# inverter.net
KiCad netlist of a schematic drawn in EAGLE
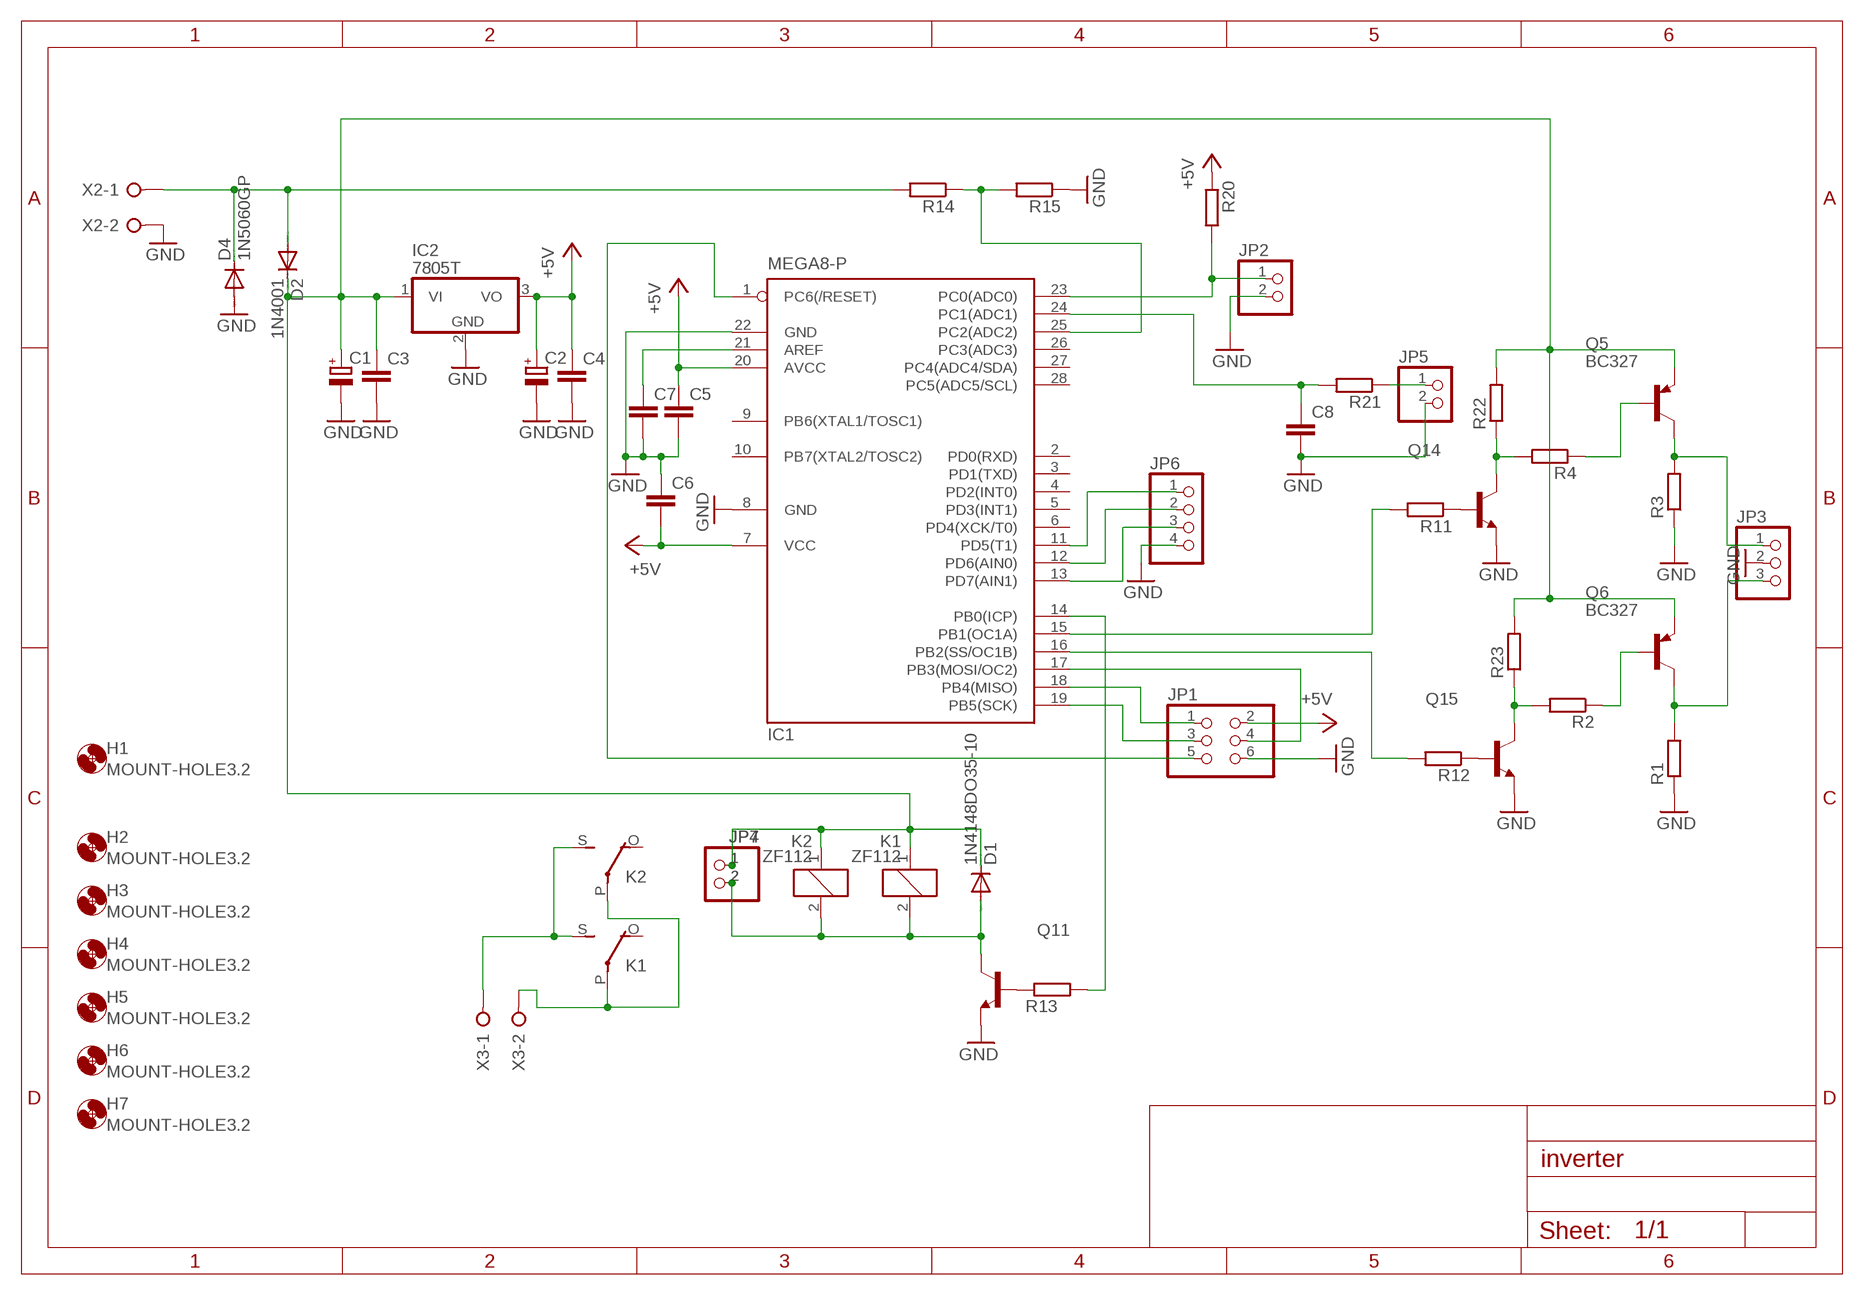
[diagram p0: schematic, sheet 1]

(export (version "E")
  (design (tool "Eeschema 10.0.6"))
  (components
    (comp (ref "C1")
      (value "CPOL-EUE7.5-16")
      (footprint "eagle-import:E7,5-16")
      (libsource (lib "eagle-import") (part "CPOL-EUE7.5-16"))
    )
    (comp (ref "C2")
      (value "CPOL-EUE2.5-6")
      (footprint "eagle-import:E2,5-6")
      (libsource (lib "eagle-import") (part "CPOL-EUE2.5-6"))
    )
    (comp (ref "C3")
      (value "C-EU050-025X075")
      (footprint "eagle-import:C050-025X075")
      (libsource (lib "eagle-import") (part "C-EU050-025X075"))
    )
    (comp (ref "C4")
      (value "C-EU050-025X075")
      (footprint "eagle-import:C050-025X075")
      (libsource (lib "eagle-import") (part "C-EU050-025X075"))
    )
    (comp (ref "C5")
      (value "C-EU050-025X075")
      (footprint "eagle-import:C050-025X075")
      (libsource (lib "eagle-import") (part "C-EU050-025X075"))
    )
    (comp (ref "C6")
      (value "C-EU050-025X075")
      (footprint "eagle-import:C050-025X075")
      (libsource (lib "eagle-import") (part "C-EU050-025X075"))
    )
    (comp (ref "C7")
      (value "C-EU050-025X075")
      (footprint "eagle-import:C050-025X075")
      (libsource (lib "eagle-import") (part "C-EU050-025X075"))
    )
    (comp (ref "C8")
      (value "C-EU050-025X075")
      (footprint "eagle-import:C050-025X075")
      (libsource (lib "eagle-import") (part "C-EU050-025X075"))
    )
    (comp (ref "D1")
      (value "1N4148DO35-10")
      (footprint "eagle-import:DO35-10")
      (libsource (lib "eagle-import") (part "1N4148DO35-10"))
    )
    (comp (ref "D2")
      (value "1N4001")
      (footprint "eagle-import:DO35-10")
      (libsource (lib "eagle-import") (part "1N4148DO35-10"))
    )
    (comp (ref "D4")
      (value "1N5060GP")
      (footprint "eagle-import:DO15-12")
      (libsource (lib "eagle-import") (part "1N5060GP"))
    )
    (comp (ref "H1")
      (value "MOUNT-HOLE3.2")
      (footprint "eagle-import:3,2")
      (libsource (lib "eagle-import") (part "MOUNT-HOLE3.2"))
    )
    (comp (ref "H2")
      (value "MOUNT-HOLE3.2")
      (footprint "eagle-import:3,2")
      (libsource (lib "eagle-import") (part "MOUNT-HOLE3.2"))
    )
    (comp (ref "H3")
      (value "MOUNT-HOLE3.2")
      (footprint "eagle-import:3,2")
      (libsource (lib "eagle-import") (part "MOUNT-HOLE3.2"))
    )
    (comp (ref "H4")
      (value "MOUNT-HOLE3.2")
      (footprint "eagle-import:3,2")
      (libsource (lib "eagle-import") (part "MOUNT-HOLE3.2"))
    )
    (comp (ref "H5")
      (value "MOUNT-HOLE3.2")
      (footprint "eagle-import:3,2")
      (libsource (lib "eagle-import") (part "MOUNT-HOLE3.2"))
    )
    (comp (ref "H6")
      (value "MOUNT-HOLE3.2")
      (footprint "eagle-import:3,2")
      (libsource (lib "eagle-import") (part "MOUNT-HOLE3.2"))
    )
    (comp (ref "H7")
      (value "MOUNT-HOLE3.2")
      (footprint "eagle-import:3,2")
      (libsource (lib "eagle-import") (part "MOUNT-HOLE3.2"))
    )
    (comp (ref "IC1")
      (value "MEGA8-P")
      (footprint "eagle-import:DIL28-3")
      (libsource (lib "eagle-import") (part "MEGA8-P"))
    )
    (comp (ref "IC2")
      (value "7805T")
      (footprint "eagle-import:TO220H")
      (libsource (lib "eagle-import") (part "78T05"))
    )
    (comp (ref "JP1")
      (value "PINHD-2X3")
      (footprint "eagle-import:2X03")
      (libsource (lib "eagle-import") (part "PINHD-2X3"))
    )
    (comp (ref "JP2")
      (value "PINHD-1X2")
      (footprint "eagle-import:1X02")
      (libsource (lib "eagle-import") (part "PINHD-1X2"))
    )
    (comp (ref "JP3")
      (value "PINHD-1X3")
      (footprint "eagle-import:1X03")
      (libsource (lib "eagle-import") (part "PINHD-1X3"))
    )
    (comp (ref "JP4")
      (value "PINHD-1X2")
      (footprint "eagle-import:1X02")
      (libsource (lib "eagle-import") (part "PINHD-1X2"))
    )
    (comp (ref "JP5")
      (value "PINHD-1X2")
      (footprint "eagle-import:1X02")
      (libsource (lib "eagle-import") (part "PINHD-1X2"))
    )
    (comp (ref "JP6")
      (value "PINHD-1X4")
      (footprint "eagle-import:1X04")
      (libsource (lib "eagle-import") (part "PINHD-1X4"))
    )
    (comp (ref "JP7")
      (value "PINHD-1X2")
      (footprint "eagle-import:1X02")
      (libsource (lib "eagle-import") (part "PINHD-1X2"))
    )
    (comp (ref "K1")
      (value "ZF112")
      (footprint "eagle-import:ZF112")
      (libsource (lib "eagle-import") (part "ZF112"))
    )
    (comp (ref "K2")
      (value "ZF112")
      (footprint "eagle-import:ZF112")
      (libsource (lib "eagle-import") (part "ZF112"))
    )
    (comp (ref "Q5")
      (value "BC327")
      (footprint "eagle-import:TO92-EBC")
      (libsource (lib "eagle-import") (part "BC327"))
    )
    (comp (ref "Q6")
      (value "BC327")
      (footprint "eagle-import:TO92-EBC")
      (libsource (lib "eagle-import") (part "BC327"))
    )
    (comp (ref "Q11")
      (value "BC547-NPN-TO92-CBE")
      (footprint "eagle-import:TO92-CBE")
      (libsource (lib "eagle-import") (part "-NPN-TO92-CBEBC547"))
    )
    (comp (ref "Q14")
      (value "BC547-NPN-TO92-CBE")
      (footprint "eagle-import:TO92-CBE")
      (libsource (lib "eagle-import") (part "-NPN-TO92-CBEBC547"))
    )
    (comp (ref "Q15")
      (value "BC547-NPN-TO92-CBE")
      (footprint "eagle-import:TO92-CBE")
      (libsource (lib "eagle-import") (part "-NPN-TO92-CBEBC547"))
    )
    (comp (ref "R1")
      (value "R-EU_0207/5V")
      (footprint "eagle-import:0207_5V")
      (libsource (lib "eagle-import") (part "R-EU_0207/5V"))
    )
    (comp (ref "R2")
      (value "R-EU_0207/2V")
      (footprint "eagle-import:0207_2V")
      (libsource (lib "eagle-import") (part "R-EU_0207/2V"))
    )
    (comp (ref "R3")
      (value "R-EU_0207/5V")
      (footprint "eagle-import:0207_5V")
      (libsource (lib "eagle-import") (part "R-EU_0207/5V"))
    )
    (comp (ref "R4")
      (value "R-EU_0207/2V")
      (footprint "eagle-import:0207_2V")
      (libsource (lib "eagle-import") (part "R-EU_0207/2V"))
    )
    (comp (ref "R11")
      (value "R-EU_0207/5V")
      (footprint "eagle-import:0207_5V")
      (libsource (lib "eagle-import") (part "R-EU_0207/5V"))
    )
    (comp (ref "R12")
      (value "R-EU_0207/5V")
      (footprint "eagle-import:0207_5V")
      (libsource (lib "eagle-import") (part "R-EU_0207/5V"))
    )
    (comp (ref "R13")
      (value "R-EU_0207/2V")
      (footprint "eagle-import:0207_2V")
      (libsource (lib "eagle-import") (part "R-EU_0207/2V"))
    )
    (comp (ref "R14")
      (value "R-EU_0207/10")
      (footprint "eagle-import:0207_10")
      (libsource (lib "eagle-import") (part "R-EU_0207/10"))
    )
    (comp (ref "R15")
      (value "R-EU_0207/10")
      (footprint "eagle-import:0207_10")
      (libsource (lib "eagle-import") (part "R-EU_0207/10"))
    )
    (comp (ref "R20")
      (value "R-EU_0207/10")
      (footprint "eagle-import:0207_10")
      (libsource (lib "eagle-import") (part "R-EU_0207/10"))
    )
    (comp (ref "R21")
      (value "R-EU_0207/2V")
      (footprint "eagle-import:0207_2V")
      (libsource (lib "eagle-import") (part "R-EU_0207/2V"))
    )
    (comp (ref "R22")
      (value "R-EU_0207/10")
      (footprint "eagle-import:0207_10")
      (libsource (lib "eagle-import") (part "R-EU_0207/10"))
    )
    (comp (ref "R23")
      (value "R-EU_0207/10")
      (footprint "eagle-import:0207_10")
      (libsource (lib "eagle-import") (part "R-EU_0207/10"))
    )
    (comp (ref "X2")
      (value "W237-02P")
      (footprint "eagle-import:W237-132")
      (libsource (lib "eagle-import") (part "W237-02P"))
    )
    (comp (ref "X3")
      (value "W237-02P")
      (footprint "eagle-import:W237-132")
      (libsource (lib "eagle-import") (part "W237-02P"))
    )
  )
  (nets
    (net (code "1") (name "+5V") (class "Default")
      (node (ref "C2") (pin "+") (pinfunction "+_+") (pintype "passive"))
      (node (ref "C4") (pin "1") (pinfunction "1_1") (pintype "passive"))
      (node (ref "C5") (pin "1") (pinfunction "1_1") (pintype "passive"))
      (node (ref "C6") (pin "2") (pinfunction "2_2") (pintype "passive"))
      (node (ref "IC1") (pin "20") (pinfunction "AVCC_20") (pintype "power_in"))
      (node (ref "IC1") (pin "7") (pinfunction "VCC_7") (pintype "power_in"))
      (node (ref "IC2") (pin "3") (pinfunction "VO_3") (pintype "passive"))
      (node (ref "JP1") (pin "2") (pinfunction "2_2") (pintype "passive"))
      (node (ref "R20") (pin "1") (pinfunction "1_1") (pintype "passive"))
    )
    (net (code "2") (name "GND") (class "Default")
      (node (ref "C1") (pin "-") (pinfunction "-_-") (pintype "passive"))
      (node (ref "C2") (pin "-") (pinfunction "-_-") (pintype "passive"))
      (node (ref "C3") (pin "2") (pinfunction "2_2") (pintype "passive"))
      (node (ref "C4") (pin "2") (pinfunction "2_2") (pintype "passive"))
      (node (ref "C5") (pin "2") (pinfunction "2_2") (pintype "passive"))
      (node (ref "C6") (pin "1") (pinfunction "1_1") (pintype "passive"))
      (node (ref "C7") (pin "2") (pinfunction "2_2") (pintype "passive"))
      (node (ref "C8") (pin "2") (pinfunction "2_2") (pintype "passive"))
      (node (ref "D4") (pin "A") (pinfunction "A_A") (pintype "passive"))
      (node (ref "IC1") (pin "22") (pinfunction "GND_22") (pintype "power_in"))
      (node (ref "IC1") (pin "8") (pinfunction "GND_8") (pintype "power_in"))
      (node (ref "IC2") (pin "2") (pinfunction "GND_2") (pintype "passive"))
      (node (ref "JP1") (pin "6") (pinfunction "6_6") (pintype "passive"))
      (node (ref "JP2") (pin "2") (pinfunction "2_2") (pintype "passive"))
      (node (ref "JP3") (pin "2") (pinfunction "2_2") (pintype "passive"))
      (node (ref "JP5") (pin "2") (pinfunction "2_2") (pintype "passive"))
      (node (ref "JP6") (pin "4") (pinfunction "4_4") (pintype "passive"))
      (node (ref "Q11") (pin "E") (pinfunction "E_E") (pintype "passive"))
      (node (ref "Q14") (pin "E") (pinfunction "E_E") (pintype "passive"))
      (node (ref "Q15") (pin "E") (pinfunction "E_E") (pintype "passive"))
      (node (ref "R1") (pin "1") (pinfunction "1_1") (pintype "passive"))
      (node (ref "R15") (pin "1") (pinfunction "1_1") (pintype "passive"))
      (node (ref "R3") (pin "1") (pinfunction "1_1") (pintype "passive"))
      (node (ref "X2") (pin "2") (pinfunction "KL_2") (pintype "passive"))
    )
    (net (code "3") (name "Net-(D1-PadA)") (class "Default")
      (node (ref "D1") (pin "A") (pinfunction "A_A") (pintype "passive"))
      (node (ref "JP4") (pin "2") (pinfunction "2_2") (pintype "passive"))
      (node (ref "JP7") (pin "2") (pinfunction "2_2") (pintype "passive"))
      (node (ref "K1") (pin "2") (pinfunction "2_2") (pintype "passive"))
      (node (ref "K2") (pin "2") (pinfunction "2_2") (pintype "passive"))
      (node (ref "Q11") (pin "C") (pinfunction "C_C") (pintype "passive"))
    )
    (net (code "4") (name "Net-(IC1-AREF)") (class "Default")
      (node (ref "C7") (pin "1") (pinfunction "1_1") (pintype "passive"))
      (node (ref "IC1") (pin "21") (pinfunction "AREF_21") (pintype "passive"))
    )
    (net (code "5") (name "Net-(IC1-PB0(ICP))") (class "Default")
      (node (ref "IC1") (pin "14") (pinfunction "PB0(ICP)_14") (pintype "bidirectional"))
      (node (ref "R13") (pin "2") (pinfunction "2_2") (pintype "passive"))
    )
    (net (code "6") (name "Net-(IC1-PB1(OC1A))") (class "Default")
      (node (ref "IC1") (pin "15") (pinfunction "PB1(OC1A)_15") (pintype "bidirectional"))
      (node (ref "R11") (pin "2") (pinfunction "2_2") (pintype "passive"))
    )
    (net (code "7") (name "Net-(IC1-PB2(SS{slash}OC1B))") (class "Default")
      (node (ref "IC1") (pin "16") (pinfunction "PB2(SS/OC1B)_16") (pintype "bidirectional"))
      (node (ref "R12") (pin "2") (pinfunction "2_2") (pintype "passive"))
    )
    (net (code "8") (name "Net-(IC1-PB3(MOSI{slash}OC2))") (class "Default")
      (node (ref "IC1") (pin "17") (pinfunction "PB3(MOSI/OC2)_17") (pintype "bidirectional"))
      (node (ref "JP1") (pin "4") (pinfunction "4_4") (pintype "passive"))
    )
    (net (code "9") (name "Net-(IC1-PB4(MISO))") (class "Default")
      (node (ref "IC1") (pin "18") (pinfunction "PB4(MISO)_18") (pintype "bidirectional"))
      (node (ref "JP1") (pin "1") (pinfunction "1_1") (pintype "passive"))
    )
    (net (code "10") (name "Net-(IC1-PB5(SCK))") (class "Default")
      (node (ref "IC1") (pin "19") (pinfunction "PB5(SCK)_19") (pintype "bidirectional"))
      (node (ref "JP1") (pin "3") (pinfunction "3_3") (pintype "passive"))
    )
    (net (code "11") (name "Net-(IC1-PC0(ADC0))") (class "Default")
      (node (ref "IC1") (pin "23") (pinfunction "PC0(ADC0)_23") (pintype "bidirectional"))
      (node (ref "JP2") (pin "1") (pinfunction "1_1") (pintype "passive"))
      (node (ref "R20") (pin "2") (pinfunction "2_2") (pintype "passive"))
    )
    (net (code "12") (name "Net-(IC1-PC1(ADC1))") (class "Default")
      (node (ref "C8") (pin "1") (pinfunction "1_1") (pintype "passive"))
      (node (ref "IC1") (pin "24") (pinfunction "PC1(ADC1)_24") (pintype "bidirectional"))
      (node (ref "R21") (pin "2") (pinfunction "2_2") (pintype "passive"))
    )
    (net (code "13") (name "Net-(IC1-PC2(ADC2))") (class "Default")
      (node (ref "IC1") (pin "25") (pinfunction "PC2(ADC2)_25") (pintype "bidirectional"))
      (node (ref "R14") (pin "1") (pinfunction "1_1") (pintype "passive"))
      (node (ref "R15") (pin "2") (pinfunction "2_2") (pintype "passive"))
    )
    (net (code "14") (name "Net-(IC1-PC6({slash}RESET))") (class "Default")
      (node (ref "IC1") (pin "1") (pinfunction "PC6(/RESET)_1") (pintype "bidirectional"))
      (node (ref "JP1") (pin "5") (pinfunction "5_5") (pintype "passive"))
    )
    (net (code "15") (name "Net-(IC1-PD5(T1))") (class "Default")
      (node (ref "IC1") (pin "11") (pinfunction "PD5(T1)_11") (pintype "bidirectional"))
      (node (ref "JP6") (pin "1") (pinfunction "1_1") (pintype "passive"))
    )
    (net (code "16") (name "Net-(IC1-PD6(AIN0))") (class "Default")
      (node (ref "IC1") (pin "12") (pinfunction "PD6(AIN0)_12") (pintype "bidirectional"))
      (node (ref "JP6") (pin "2") (pinfunction "2_2") (pintype "passive"))
    )
    (net (code "17") (name "Net-(IC1-PD7(AIN1))") (class "Default")
      (node (ref "IC1") (pin "13") (pinfunction "PD7(AIN1)_13") (pintype "bidirectional"))
      (node (ref "JP6") (pin "3") (pinfunction "3_3") (pintype "passive"))
    )
    (net (code "18") (name "Net-(IC2-VI)") (class "Default")
      (node (ref "C1") (pin "+") (pinfunction "+_+") (pintype "passive"))
      (node (ref "C3") (pin "1") (pinfunction "1_1") (pintype "passive"))
      (node (ref "D1") (pin "C") (pinfunction "C_C") (pintype "passive"))
      (node (ref "D2") (pin "C") (pinfunction "C_C") (pintype "passive"))
      (node (ref "IC2") (pin "1") (pinfunction "VI_1") (pintype "input"))
      (node (ref "JP4") (pin "1") (pinfunction "1_1") (pintype "passive"))
      (node (ref "JP7") (pin "1") (pinfunction "1_1") (pintype "passive"))
      (node (ref "K1") (pin "1") (pinfunction "1_1") (pintype "passive"))
      (node (ref "K2") (pin "1") (pinfunction "1_1") (pintype "passive"))
      (node (ref "Q5") (pin "E") (pinfunction "E_E") (pintype "passive"))
      (node (ref "Q6") (pin "E") (pinfunction "E_E") (pintype "passive"))
      (node (ref "R22") (pin "2") (pinfunction "2_2") (pintype "passive"))
      (node (ref "R23") (pin "2") (pinfunction "2_2") (pintype "passive"))
    )
    (net (code "19") (name "Net-(JP3-Pad1)") (class "Default")
      (node (ref "JP3") (pin "1") (pinfunction "1_1") (pintype "passive"))
      (node (ref "Q5") (pin "C") (pinfunction "C_C") (pintype "passive"))
      (node (ref "R3") (pin "2") (pinfunction "2_2") (pintype "passive"))
    )
    (net (code "20") (name "Net-(JP3-Pad3)") (class "Default")
      (node (ref "JP3") (pin "3") (pinfunction "3_3") (pintype "passive"))
      (node (ref "Q6") (pin "C") (pinfunction "C_C") (pintype "passive"))
      (node (ref "R1") (pin "2") (pinfunction "2_2") (pintype "passive"))
    )
    (net (code "21") (name "Net-(JP5-Pad1)") (class "Default")
      (node (ref "JP5") (pin "1") (pinfunction "1_1") (pintype "passive"))
      (node (ref "R21") (pin "1") (pinfunction "1_1") (pintype "passive"))
    )
    (net (code "22") (name "Net-(Q5-PadB)") (class "Default")
      (node (ref "Q5") (pin "B") (pinfunction "B_B") (pintype "passive"))
      (node (ref "R4") (pin "1") (pinfunction "1_1") (pintype "passive"))
    )
    (net (code "23") (name "Net-(Q6-PadB)") (class "Default")
      (node (ref "Q6") (pin "B") (pinfunction "B_B") (pintype "passive"))
      (node (ref "R2") (pin "1") (pinfunction "1_1") (pintype "passive"))
    )
    (net (code "24") (name "Net-(Q11-PadB)") (class "Default")
      (node (ref "Q11") (pin "B") (pinfunction "B_B") (pintype "passive"))
      (node (ref "R13") (pin "1") (pinfunction "1_1") (pintype "passive"))
    )
    (net (code "25") (name "Net-(Q14-PadB)") (class "Default")
      (node (ref "Q14") (pin "B") (pinfunction "B_B") (pintype "passive"))
      (node (ref "R11") (pin "1") (pinfunction "1_1") (pintype "passive"))
    )
    (net (code "26") (name "Net-(Q14-PadC)") (class "Default")
      (node (ref "Q14") (pin "C") (pinfunction "C_C") (pintype "passive"))
      (node (ref "R22") (pin "1") (pinfunction "1_1") (pintype "passive"))
      (node (ref "R4") (pin "2") (pinfunction "2_2") (pintype "passive"))
    )
    (net (code "27") (name "Net-(Q15-PadB)") (class "Default")
      (node (ref "Q15") (pin "B") (pinfunction "B_B") (pintype "passive"))
      (node (ref "R12") (pin "1") (pinfunction "1_1") (pintype "passive"))
    )
    (net (code "28") (name "Net-(Q15-PadC)") (class "Default")
      (node (ref "Q15") (pin "C") (pinfunction "C_C") (pintype "passive"))
      (node (ref "R2") (pin "2") (pinfunction "2_2") (pintype "passive"))
      (node (ref "R23") (pin "1") (pinfunction "1_1") (pintype "passive"))
    )
    (net (code "29") (name "Net-(X2A-KL)") (class "Default")
      (node (ref "D2") (pin "A") (pinfunction "A_A") (pintype "passive"))
      (node (ref "D4") (pin "C") (pinfunction "C_C") (pintype "passive"))
      (node (ref "R14") (pin "2") (pinfunction "2_2") (pintype "passive"))
      (node (ref "X2") (pin "1") (pinfunction "KL_1") (pintype "passive"))
    )
    (net (code "30") (name "Net-(X3A-KL)") (class "Default")
      (node (ref "K1") (pin "S") (pinfunction "S_S") (pintype "passive"))
      (node (ref "K2") (pin "S") (pinfunction "S_S") (pintype "passive"))
      (node (ref "X3") (pin "1") (pinfunction "KL_1") (pintype "passive"))
    )
    (net (code "31") (name "Net-(X3B-KL)") (class "Default")
      (node (ref "K1") (pin "P") (pinfunction "P_P") (pintype "passive"))
      (node (ref "K2") (pin "P") (pinfunction "P_P") (pintype "passive"))
      (node (ref "X3") (pin "2") (pinfunction "KL_2") (pintype "passive"))
    )
    (net (code "32") (name "unconnected-(IC1-PB6(XTAL1{slash}TOSC1)-Pad9)") (class "Default")
      (node (ref "IC1") (pin "9") (pinfunction "PB6(XTAL1/TOSC1)_9") (pintype "bidirectional"))
    )
    (net (code "33") (name "unconnected-(IC1-PB7(XTAL2{slash}TOSC2)-Pad10)") (class "Default")
      (node (ref "IC1") (pin "10") (pinfunction "PB7(XTAL2/TOSC2)_10") (pintype "bidirectional"))
    )
    (net (code "34") (name "unconnected-(IC1-PC3(ADC3)-Pad26)") (class "Default")
      (node (ref "IC1") (pin "26") (pinfunction "PC3(ADC3)_26") (pintype "bidirectional"))
    )
    (net (code "35") (name "unconnected-(IC1-PC4(ADC4{slash}SDA)-Pad27)") (class "Default")
      (node (ref "IC1") (pin "27") (pinfunction "PC4(ADC4/SDA)_27") (pintype "bidirectional"))
    )
    (net (code "36") (name "unconnected-(IC1-PC5(ADC5{slash}SCL)-Pad28)") (class "Default")
      (node (ref "IC1") (pin "28") (pinfunction "PC5(ADC5/SCL)_28") (pintype "bidirectional"))
    )
    (net (code "37") (name "unconnected-(IC1-PD0(RXD)-Pad2)") (class "Default")
      (node (ref "IC1") (pin "2") (pinfunction "PD0(RXD)_2") (pintype "bidirectional"))
    )
    (net (code "38") (name "unconnected-(IC1-PD1(TXD)-Pad3)") (class "Default")
      (node (ref "IC1") (pin "3") (pinfunction "PD1(TXD)_3") (pintype "bidirectional"))
    )
    (net (code "39") (name "unconnected-(IC1-PD2(INT0)-Pad4)") (class "Default")
      (node (ref "IC1") (pin "4") (pinfunction "PD2(INT0)_4") (pintype "bidirectional"))
    )
    (net (code "40") (name "unconnected-(IC1-PD3(INT1)-Pad5)") (class "Default")
      (node (ref "IC1") (pin "5") (pinfunction "PD3(INT1)_5") (pintype "bidirectional"))
    )
    (net (code "41") (name "unconnected-(IC1-PD4(XCK{slash}T0)-Pad6)") (class "Default")
      (node (ref "IC1") (pin "6") (pinfunction "PD4(XCK/T0)_6") (pintype "bidirectional"))
    )
    (net (code "42") (name "unconnected-(K1-PadO)") (class "Default")
      (node (ref "K1") (pin "O") (pinfunction "O_O") (pintype "passive"))
    )
    (net (code "43") (name "unconnected-(K2-PadO)") (class "Default")
      (node (ref "K2") (pin "O") (pinfunction "O_O") (pintype "passive"))
    )
  )
)
